# LC_adapter.net
KiCad netlist of a schematic drawn in EAGLE
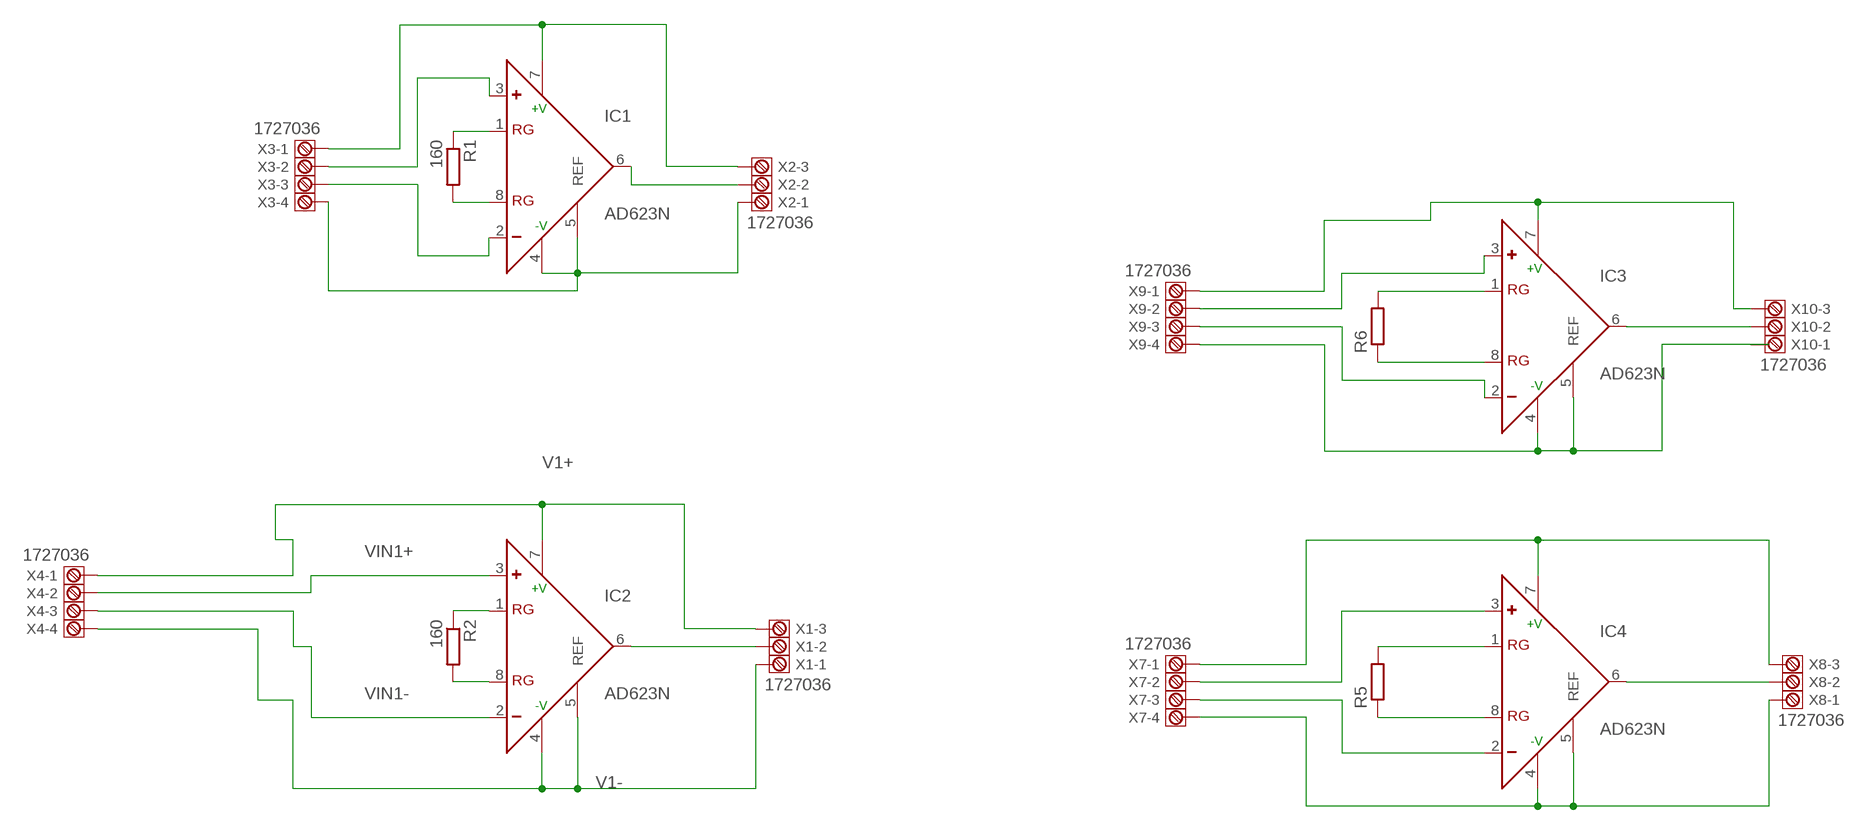
[diagram p0: schematic, sheet 1]

(export (version "E")
  (design (tool "Eeschema 10.0.6"))
  (components
    (comp (ref "IC1")
      (value "AD623N")
      (footprint "eagle-import:DIL08")
      (fields (field (name "MF") "ALTERA CORPORATION") (field (name "MPN") "AD623ANZ"))
      (libsource (lib "eagle-import") (part "AD623N"))
    )
    (comp (ref "IC2")
      (value "AD623N")
      (footprint "eagle-import:DIL08")
      (fields (field (name "MF") "ALTERA CORPORATION") (field (name "MPN") "AD623ANZ"))
      (libsource (lib "eagle-import") (part "AD623N"))
    )
    (comp (ref "IC3")
      (value "AD623N")
      (footprint "eagle-import:DIL08")
      (fields (field (name "MF") "ALTERA CORPORATION") (field (name "MPN") "AD623ANZ"))
      (libsource (lib "eagle-import") (part "AD623N"))
    )
    (comp (ref "IC4")
      (value "AD623N")
      (footprint "eagle-import:DIL08")
      (fields (field (name "MF") "ALTERA CORPORATION") (field (name "MPN") "AD623ANZ"))
      (libsource (lib "eagle-import") (part "AD623N"))
    )
    (comp (ref "R1")
      (value "160")
      (footprint "eagle-import:0204_7")
      (libsource (lib "eagle-import") (part "R-EU_0204/7"))
    )
    (comp (ref "R2")
      (value "160")
      (footprint "eagle-import:0204_7")
      (libsource (lib "eagle-import") (part "R-EU_0204/7"))
    )
    (comp (ref "R5")
      (value "R-EU_0204/7")
      (footprint "eagle-import:0204_7")
      (libsource (lib "eagle-import") (part "R-EU_0204/7"))
    )
    (comp (ref "R6")
      (value "R-EU_0204/7")
      (footprint "eagle-import:0204_7")
      (libsource (lib "eagle-import") (part "R-EU_0204/7"))
    )
    (comp (ref "X1")
      (value "1727036")
      (footprint "eagle-import:1727036")
      (fields (field (name "MF") "FARNELL"))
      (libsource (lib "eagle-import") (part "1727036"))
    )
    (comp (ref "X2")
      (value "1727036")
      (footprint "eagle-import:1727036")
      (fields (field (name "MF") "FARNELL"))
      (libsource (lib "eagle-import") (part "1727036"))
    )
    (comp (ref "X3")
      (value "1727036")
      (footprint "eagle-import:1727036")
      (fields (field (name "MF") "FARNELL"))
      (libsource (lib "eagle-import") (part "1727036"))
    )
    (comp (ref "X4")
      (value "1727036")
      (footprint "eagle-import:1727036")
      (fields (field (name "MF") "FARNELL"))
      (libsource (lib "eagle-import") (part "1727036"))
    )
    (comp (ref "X7")
      (value "1727036")
      (footprint "eagle-import:1727036")
      (fields (field (name "MF") "FARNELL"))
      (libsource (lib "eagle-import") (part "1727036"))
    )
    (comp (ref "X8")
      (value "1727036")
      (footprint "eagle-import:1727036")
      (fields (field (name "MF") "FARNELL"))
      (libsource (lib "eagle-import") (part "1727036"))
    )
    (comp (ref "X9")
      (value "1727036")
      (footprint "eagle-import:1727036")
      (fields (field (name "MF") "FARNELL"))
      (libsource (lib "eagle-import") (part "1727036"))
    )
    (comp (ref "X10")
      (value "1727036")
      (footprint "eagle-import:1727036")
      (fields (field (name "MF") "FARNELL"))
      (libsource (lib "eagle-import") (part "1727036"))
    )
  )
  (nets
    (net (code "1") (name "/V1+") (class "Default")
      (node (ref "IC2") (pin "7") (pinfunction "+V_7") (pintype "power_in"))
      (node (ref "X1") (pin "3") (pinfunction "1_3") (pintype "passive"))
      (node (ref "X4") (pin "1") (pinfunction "1_1") (pintype "passive"))
    )
    (net (code "2") (name "/V1-") (class "Default")
      (node (ref "IC2") (pin "4") (pinfunction "-V_4") (pintype "power_in"))
      (node (ref "IC2") (pin "5") (pinfunction "REF_5") (pintype "passive"))
      (node (ref "X1") (pin "1") (pinfunction "1_1") (pintype "passive"))
      (node (ref "X4") (pin "4") (pinfunction "1_4") (pintype "passive"))
    )
    (net (code "3") (name "/VIN1+") (class "Default")
      (node (ref "IC2") (pin "3") (pinfunction "+_3") (pintype "input"))
      (node (ref "X4") (pin "2") (pinfunction "1_2") (pintype "passive"))
    )
    (net (code "4") (name "/VIN1-") (class "Default")
      (node (ref "IC2") (pin "2") (pinfunction "-_2") (pintype "input"))
      (node (ref "X4") (pin "3") (pinfunction "1_3") (pintype "passive"))
    )
    (net (code "5") (name "Net-(IC1-+)") (class "Default")
      (node (ref "IC1") (pin "3") (pinfunction "+_3") (pintype "input"))
      (node (ref "X3") (pin "2") (pinfunction "1_2") (pintype "passive"))
    )
    (net (code "6") (name "Net-(IC1-+V)") (class "Default")
      (node (ref "IC1") (pin "7") (pinfunction "+V_7") (pintype "power_in"))
      (node (ref "X2") (pin "3") (pinfunction "1_3") (pintype "passive"))
      (node (ref "X3") (pin "1") (pinfunction "1_1") (pintype "passive"))
    )
    (net (code "7") (name "Net-(IC1--)") (class "Default")
      (node (ref "IC1") (pin "2") (pinfunction "-_2") (pintype "input"))
      (node (ref "X3") (pin "3") (pinfunction "1_3") (pintype "passive"))
    )
    (net (code "8") (name "Net-(IC1--V)") (class "Default")
      (node (ref "IC1") (pin "4") (pinfunction "-V_4") (pintype "power_in"))
      (node (ref "IC1") (pin "5") (pinfunction "REF_5") (pintype "passive"))
      (node (ref "X2") (pin "1") (pinfunction "1_1") (pintype "passive"))
      (node (ref "X3") (pin "4") (pinfunction "1_4") (pintype "passive"))
    )
    (net (code "9") (name "Net-(IC1-OUT)") (class "Default")
      (node (ref "IC1") (pin "6") (pinfunction "OUT_6") (pintype "output"))
      (node (ref "X2") (pin "2") (pinfunction "1_2") (pintype "passive"))
    )
    (net (code "10") (name "Net-(IC1-RG-Pad1)") (class "Default")
      (node (ref "IC1") (pin "1") (pinfunction "RG_1") (pintype "passive"))
      (node (ref "R1") (pin "1") (pinfunction "1_1") (pintype "passive"))
    )
    (net (code "11") (name "Net-(IC1-RG-Pad8)") (class "Default")
      (node (ref "IC1") (pin "8") (pinfunction "RG_8") (pintype "passive"))
      (node (ref "R1") (pin "2") (pinfunction "2_2") (pintype "passive"))
    )
    (net (code "12") (name "Net-(IC2-OUT)") (class "Default")
      (node (ref "IC2") (pin "6") (pinfunction "OUT_6") (pintype "output"))
      (node (ref "X1") (pin "2") (pinfunction "1_2") (pintype "passive"))
    )
    (net (code "13") (name "Net-(IC2-RG-Pad1)") (class "Default")
      (node (ref "IC2") (pin "1") (pinfunction "RG_1") (pintype "passive"))
      (node (ref "R2") (pin "1") (pinfunction "1_1") (pintype "passive"))
    )
    (net (code "14") (name "Net-(IC2-RG-Pad8)") (class "Default")
      (node (ref "IC2") (pin "8") (pinfunction "RG_8") (pintype "passive"))
      (node (ref "R2") (pin "2") (pinfunction "2_2") (pintype "passive"))
    )
    (net (code "15") (name "Net-(IC3-+)") (class "Default")
      (node (ref "IC3") (pin "3") (pinfunction "+_3") (pintype "input"))
      (node (ref "X9") (pin "2") (pinfunction "1_2") (pintype "passive"))
    )
    (net (code "16") (name "Net-(IC3-+V)") (class "Default")
      (node (ref "IC3") (pin "7") (pinfunction "+V_7") (pintype "power_in"))
      (node (ref "X10") (pin "3") (pinfunction "1_3") (pintype "passive"))
      (node (ref "X9") (pin "1") (pinfunction "1_1") (pintype "passive"))
    )
    (net (code "17") (name "Net-(IC3--)") (class "Default")
      (node (ref "IC3") (pin "2") (pinfunction "-_2") (pintype "input"))
      (node (ref "X9") (pin "3") (pinfunction "1_3") (pintype "passive"))
    )
    (net (code "18") (name "Net-(IC3--V)") (class "Default")
      (node (ref "IC3") (pin "4") (pinfunction "-V_4") (pintype "power_in"))
      (node (ref "IC3") (pin "5") (pinfunction "REF_5") (pintype "passive"))
      (node (ref "X9") (pin "4") (pinfunction "1_4") (pintype "passive"))
    )
    (net (code "19") (name "Net-(IC3-OUT)") (class "Default")
      (node (ref "IC3") (pin "6") (pinfunction "OUT_6") (pintype "output"))
      (node (ref "X10") (pin "2") (pinfunction "1_2") (pintype "passive"))
    )
    (net (code "20") (name "Net-(IC3-RG-Pad1)") (class "Default")
      (node (ref "IC3") (pin "1") (pinfunction "RG_1") (pintype "passive"))
      (node (ref "R6") (pin "2") (pinfunction "2_2") (pintype "passive"))
    )
    (net (code "21") (name "Net-(IC3-RG-Pad8)") (class "Default")
      (node (ref "IC3") (pin "8") (pinfunction "RG_8") (pintype "passive"))
      (node (ref "R6") (pin "1") (pinfunction "1_1") (pintype "passive"))
    )
    (net (code "22") (name "Net-(IC4-+)") (class "Default")
      (node (ref "IC4") (pin "3") (pinfunction "+_3") (pintype "input"))
      (node (ref "X7") (pin "2") (pinfunction "1_2") (pintype "passive"))
    )
    (net (code "23") (name "Net-(IC4-+V)") (class "Default")
      (node (ref "IC4") (pin "7") (pinfunction "+V_7") (pintype "power_in"))
      (node (ref "X7") (pin "1") (pinfunction "1_1") (pintype "passive"))
      (node (ref "X8") (pin "3") (pinfunction "1_3") (pintype "passive"))
    )
    (net (code "24") (name "Net-(IC4--)") (class "Default")
      (node (ref "IC4") (pin "2") (pinfunction "-_2") (pintype "input"))
      (node (ref "X7") (pin "3") (pinfunction "1_3") (pintype "passive"))
    )
    (net (code "25") (name "Net-(IC4--V)") (class "Default")
      (node (ref "IC4") (pin "4") (pinfunction "-V_4") (pintype "power_in"))
      (node (ref "IC4") (pin "5") (pinfunction "REF_5") (pintype "passive"))
      (node (ref "X7") (pin "4") (pinfunction "1_4") (pintype "passive"))
      (node (ref "X8") (pin "1") (pinfunction "1_1") (pintype "passive"))
    )
    (net (code "26") (name "Net-(IC4-OUT)") (class "Default")
      (node (ref "IC4") (pin "6") (pinfunction "OUT_6") (pintype "output"))
      (node (ref "X8") (pin "2") (pinfunction "1_2") (pintype "passive"))
    )
    (net (code "27") (name "Net-(IC4-RG-Pad1)") (class "Default")
      (node (ref "IC4") (pin "1") (pinfunction "RG_1") (pintype "passive"))
      (node (ref "R5") (pin "2") (pinfunction "2_2") (pintype "passive"))
    )
    (net (code "28") (name "Net-(IC4-RG-Pad8)") (class "Default")
      (node (ref "IC4") (pin "8") (pinfunction "RG_8") (pintype "passive"))
      (node (ref "R5") (pin "1") (pinfunction "1_1") (pintype "passive"))
    )
    (net (code "29") (name "unconnected-(X10-Pad1)") (class "Default")
      (node (ref "X10") (pin "1") (pinfunction "1_1") (pintype "passive"))
    )
  )
)
